# FY.net
KiCad netlist of a schematic drawn in EAGLE
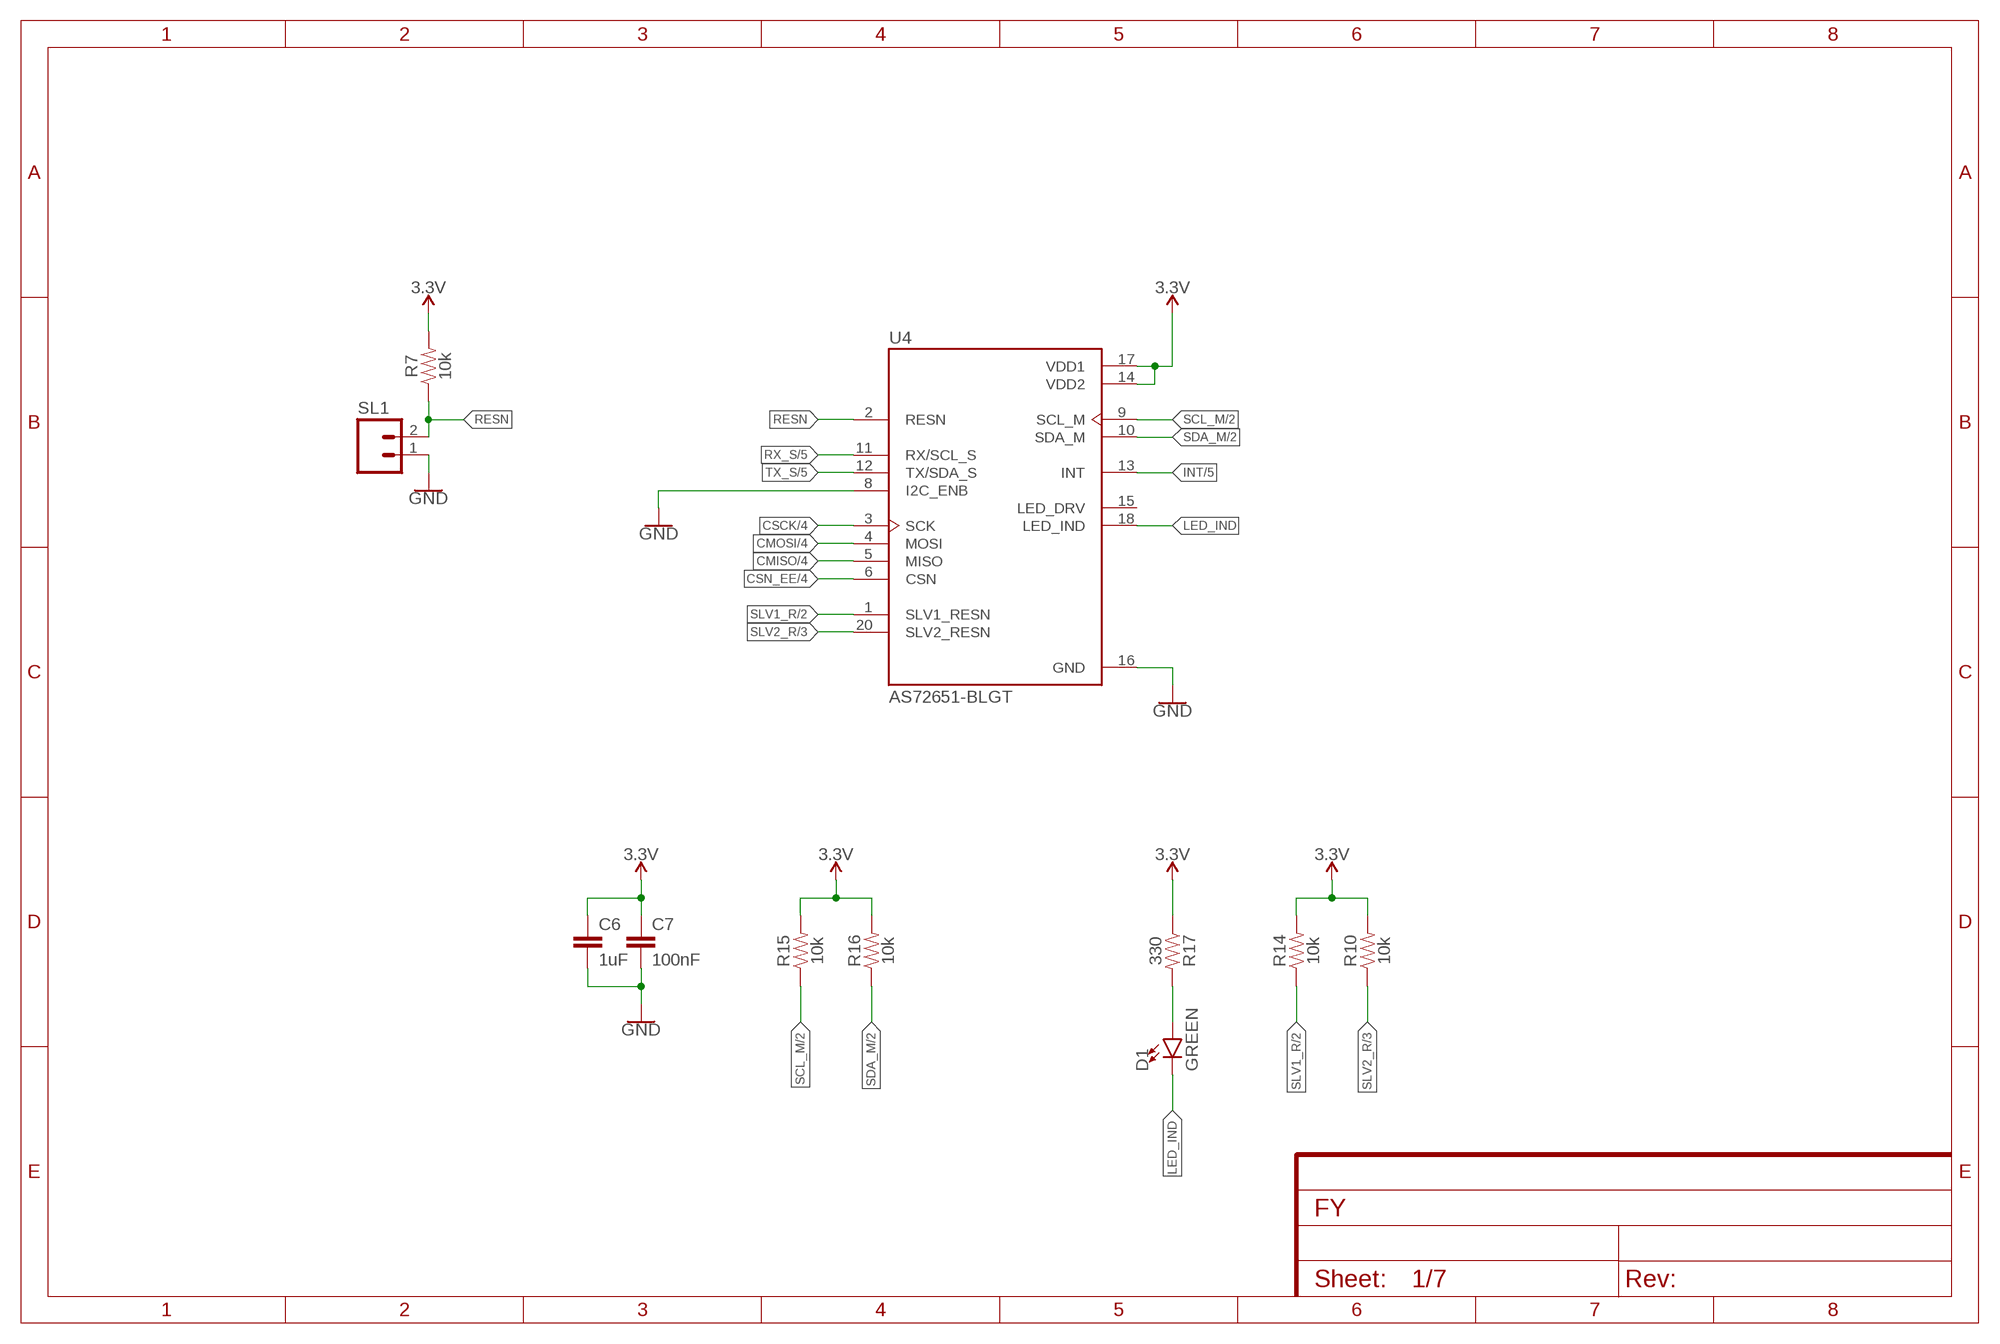
[diagram p0: schematic, sheet 1]
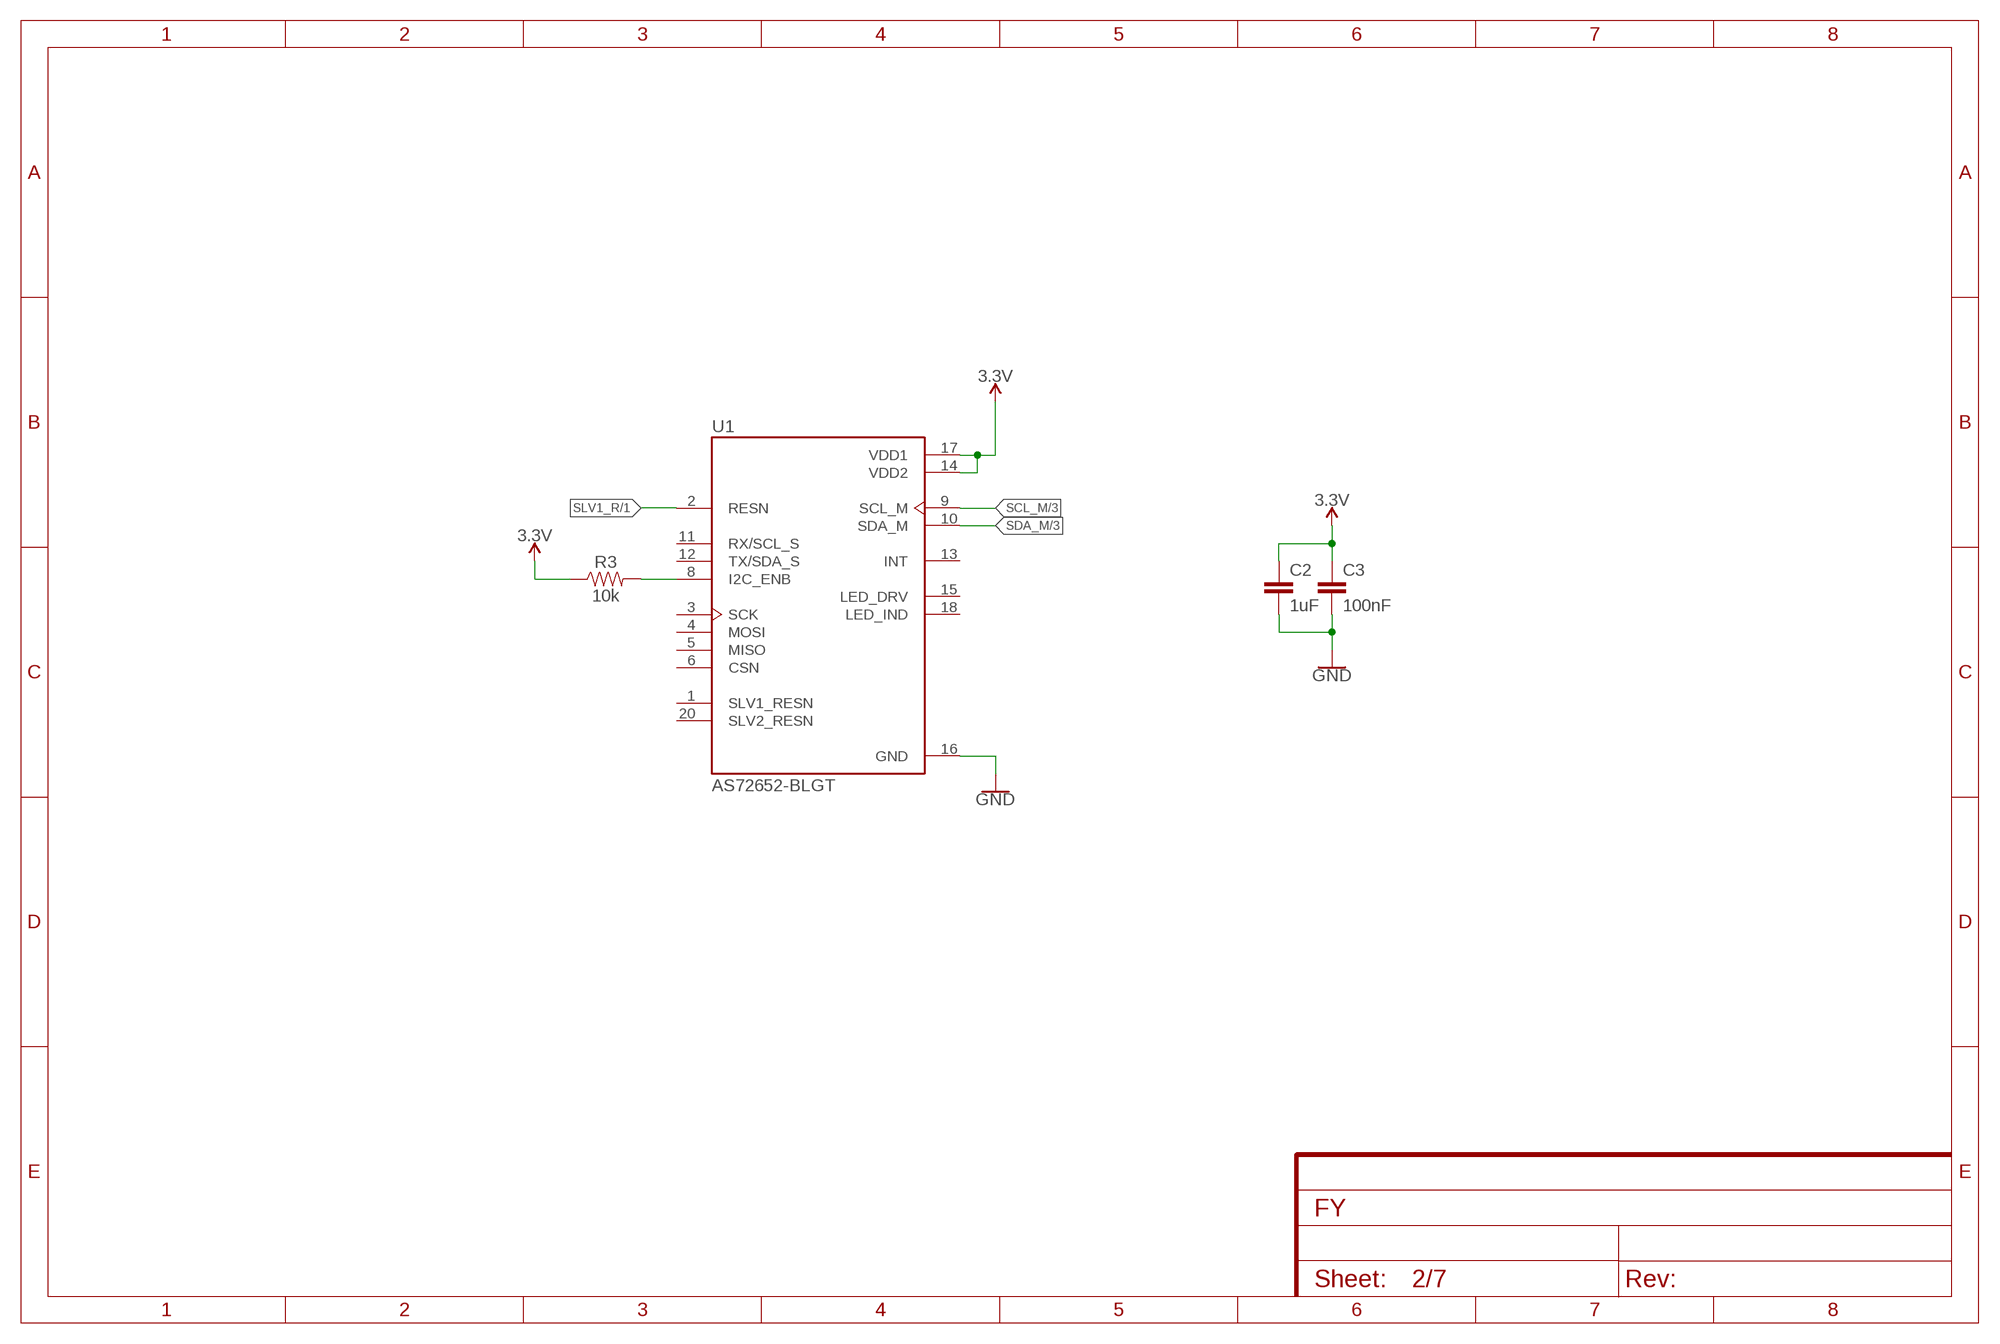
[diagram p1: schematic, sheet 2]
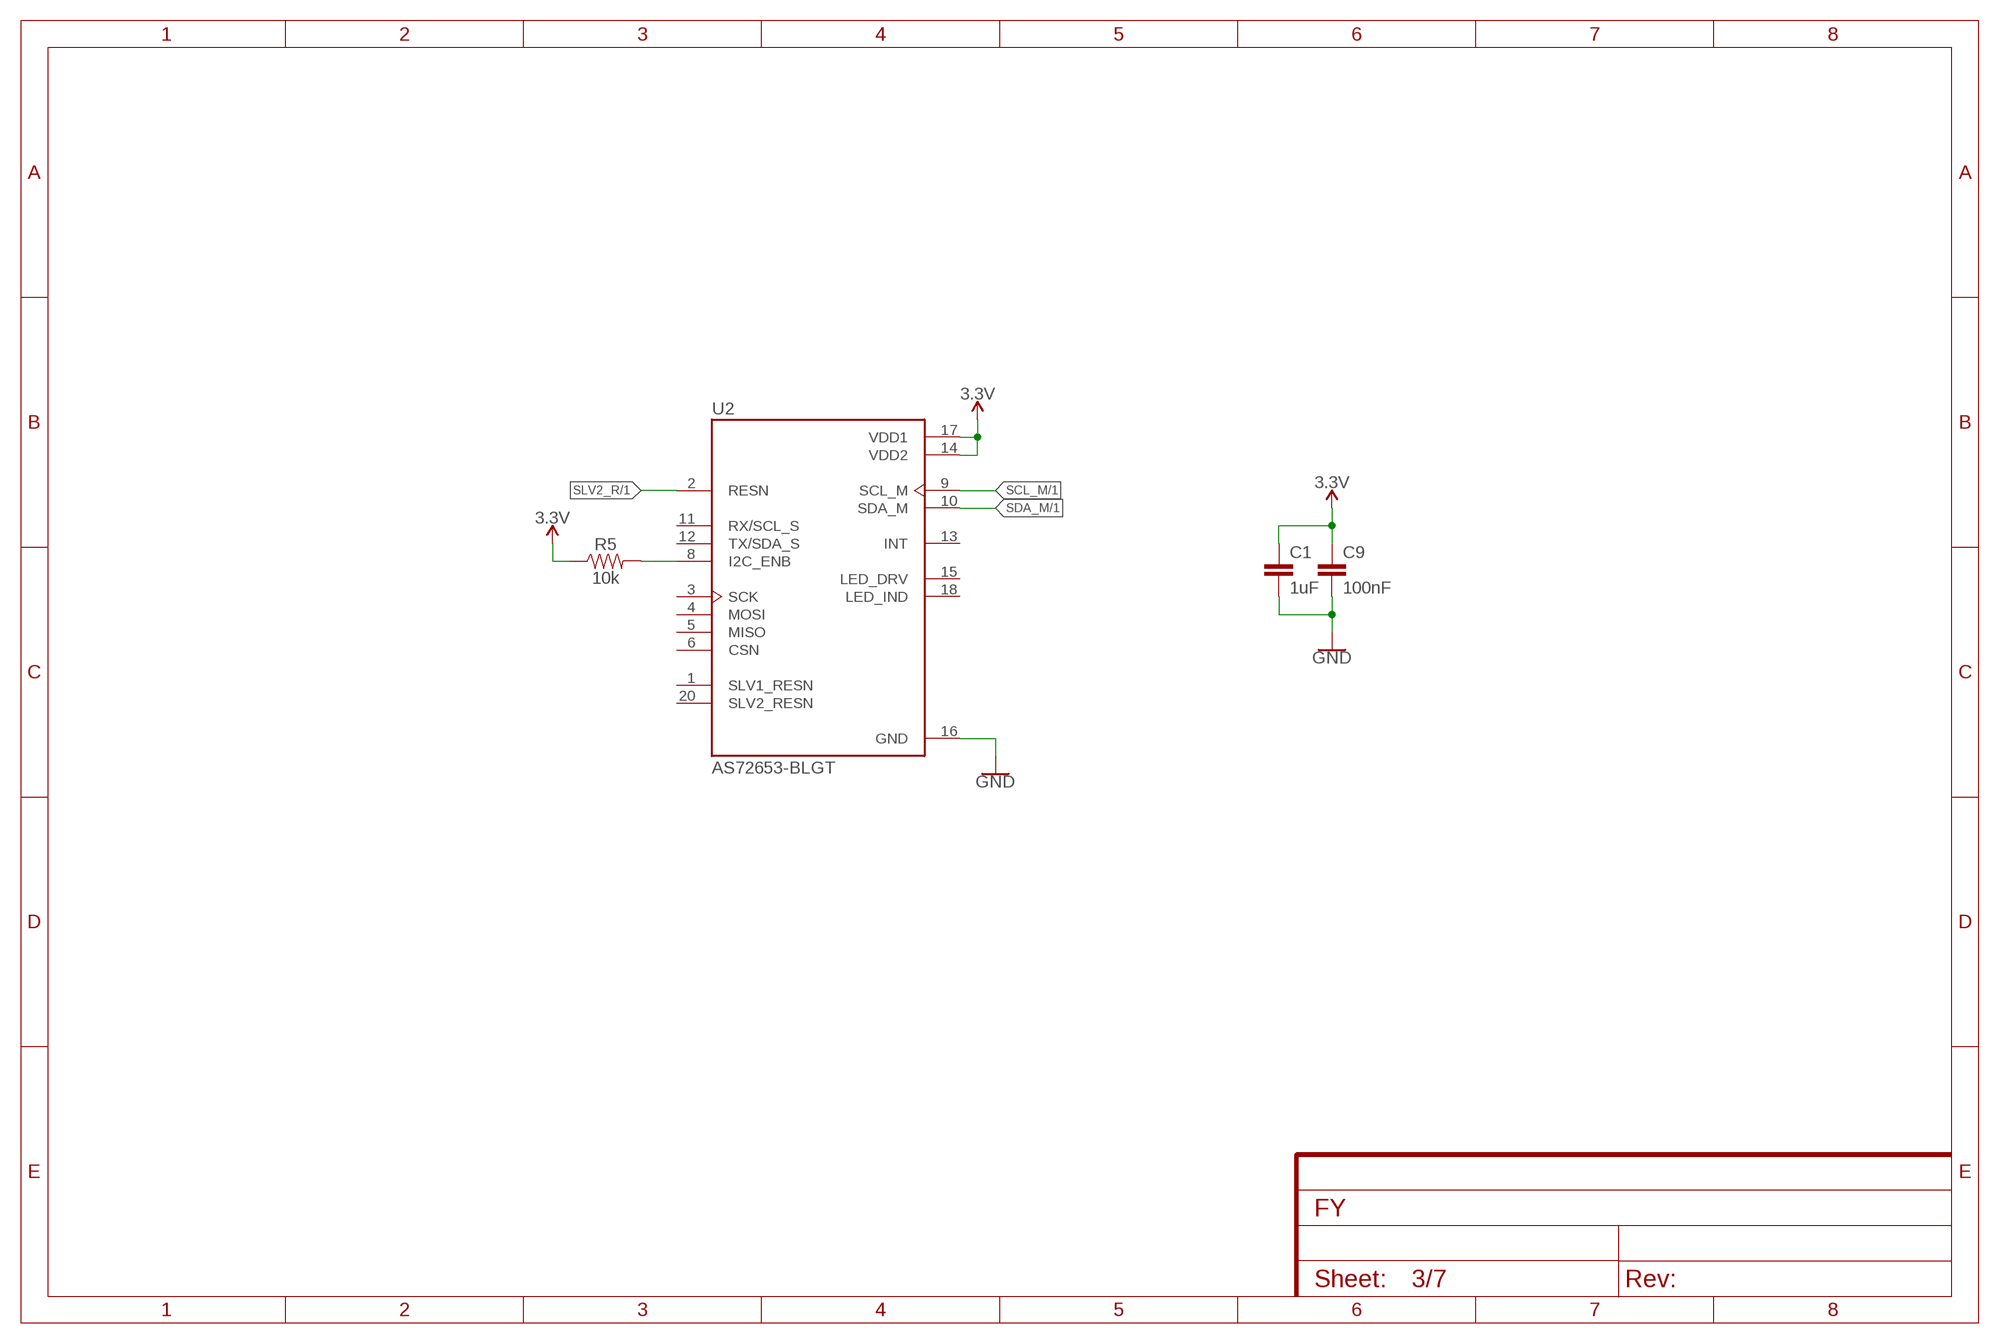
[diagram p2: schematic, sheet 3]
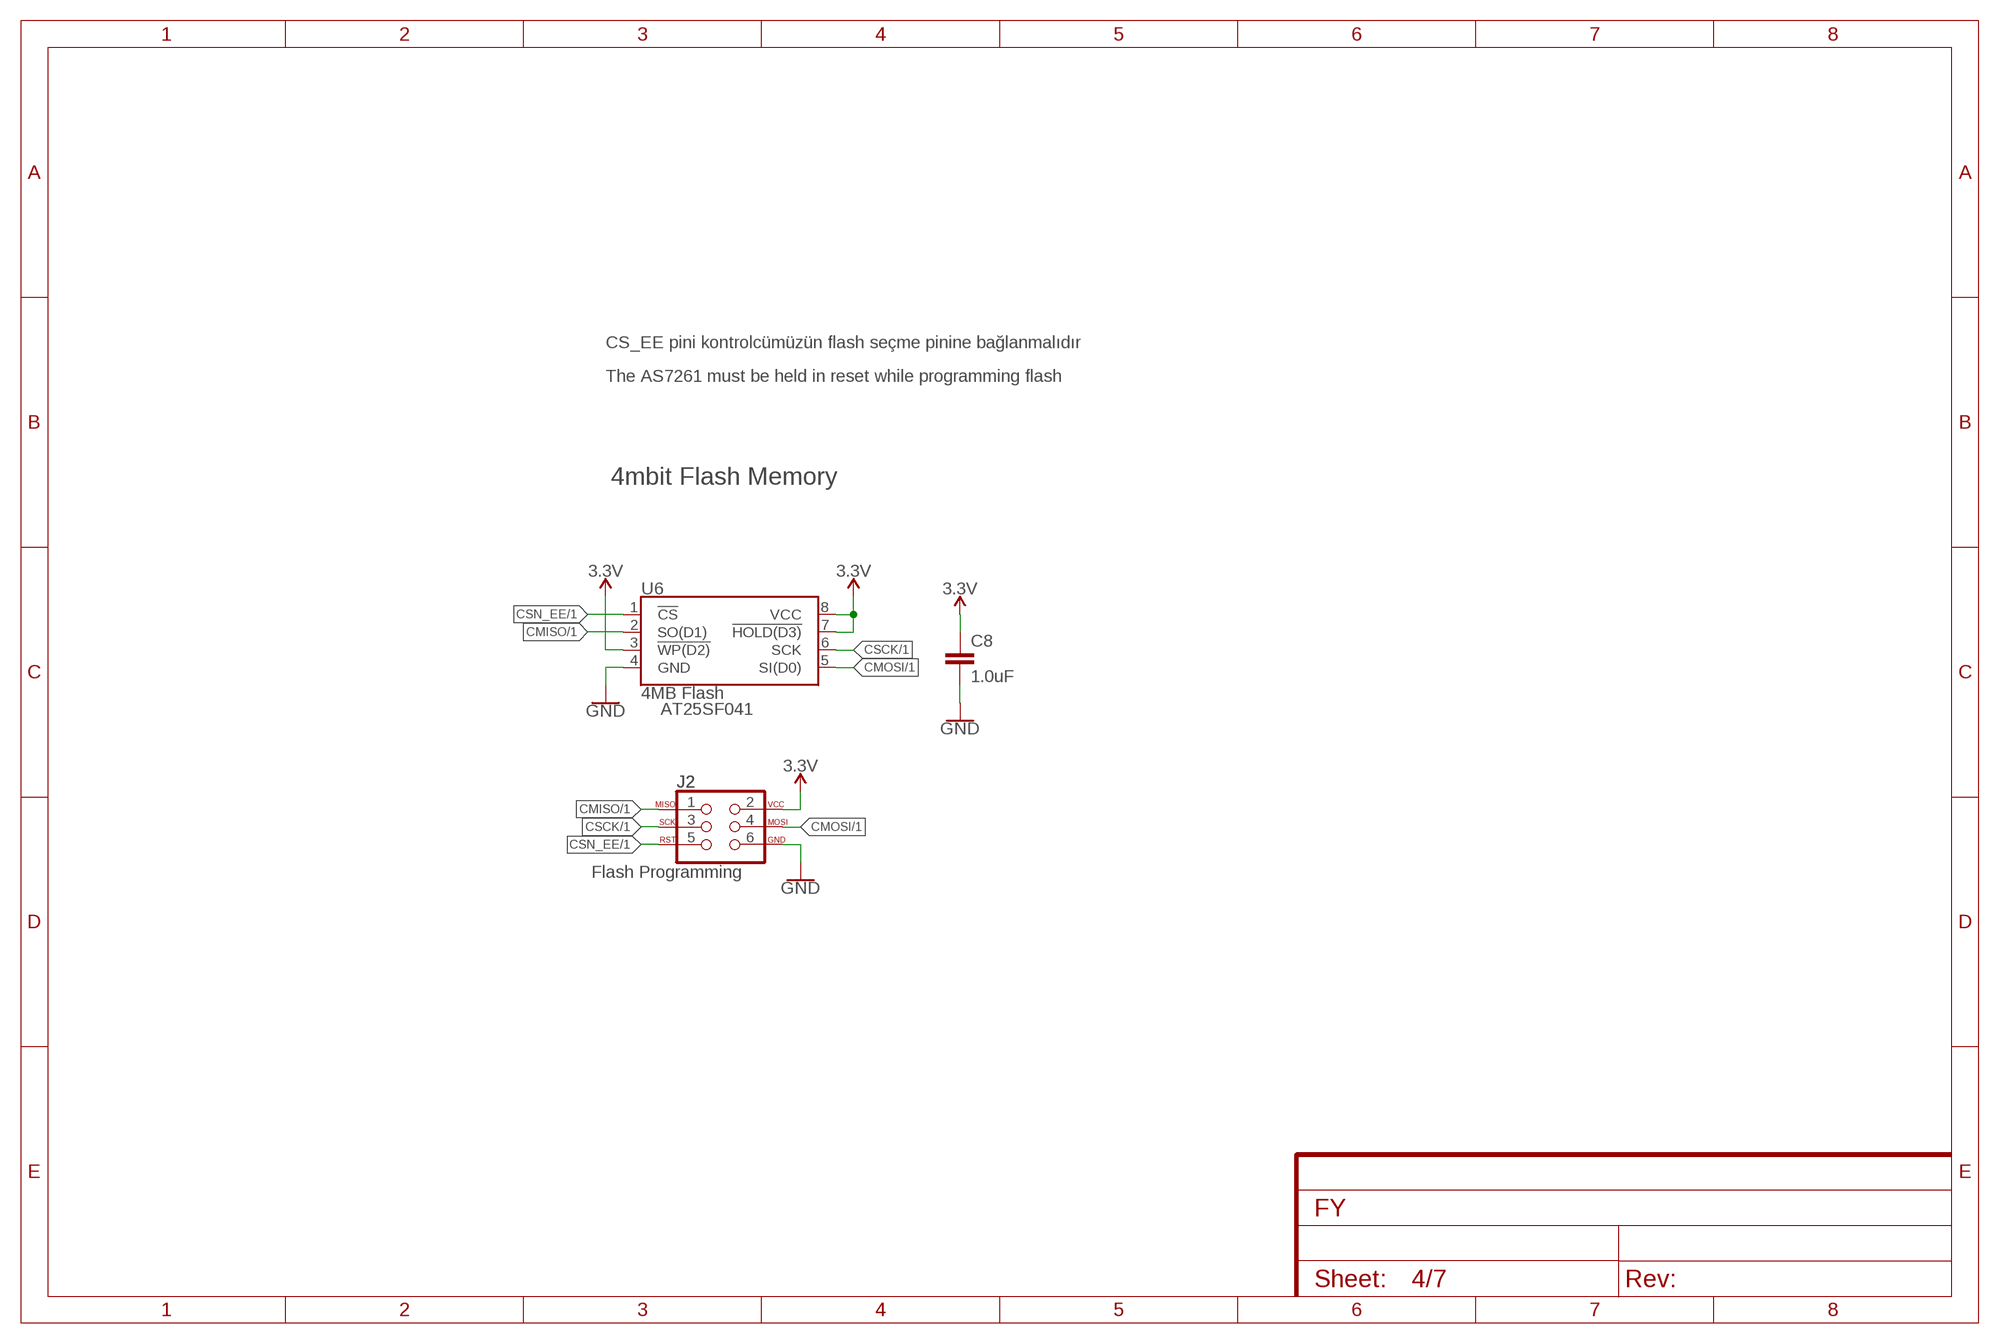
[diagram p3: schematic, sheet 4]
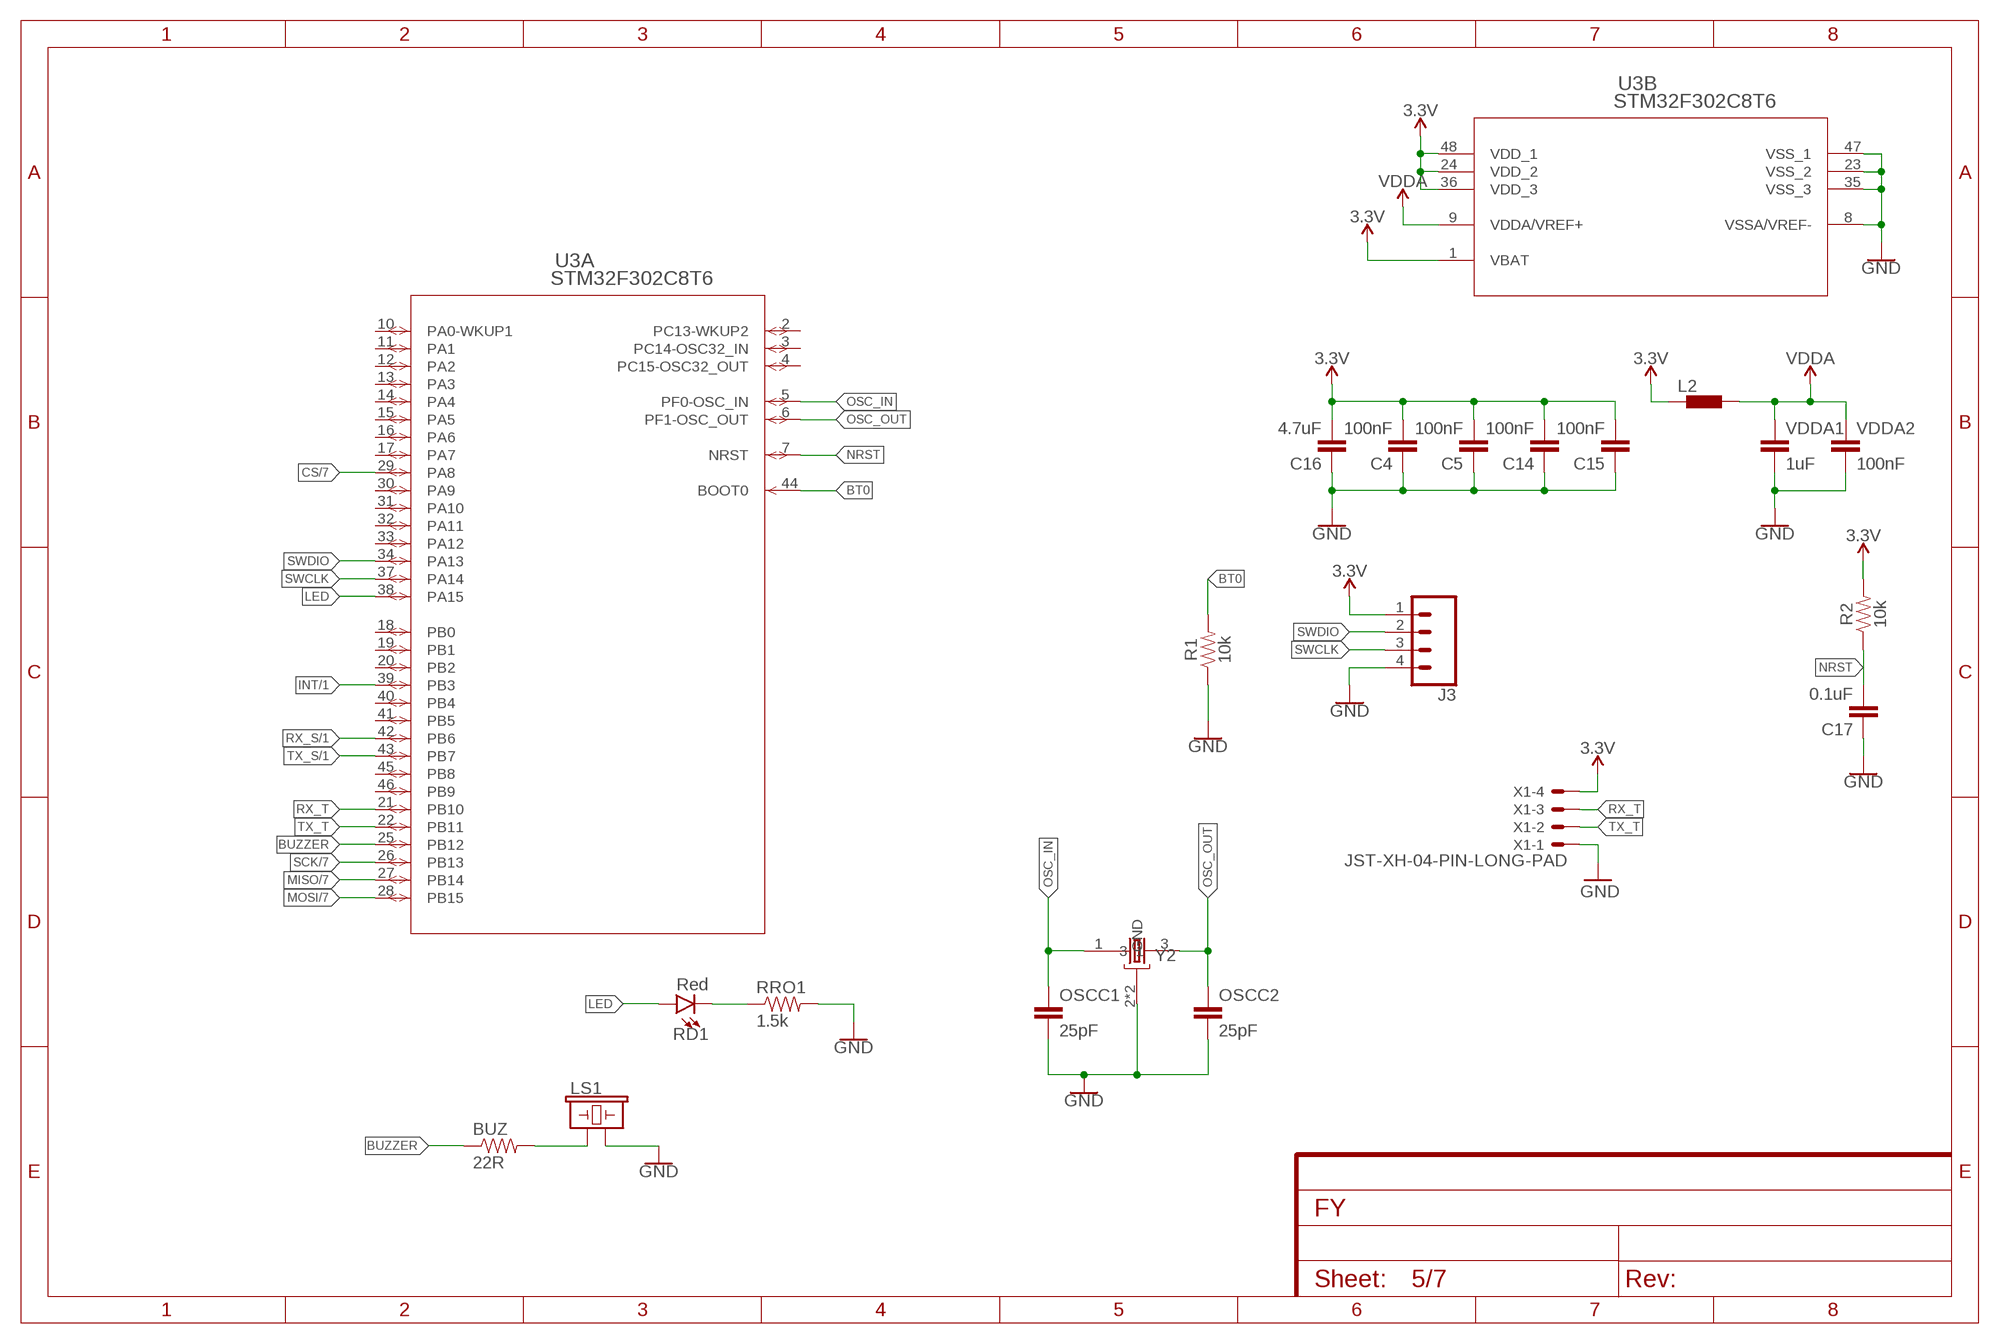
[diagram p4: schematic, sheet 5]
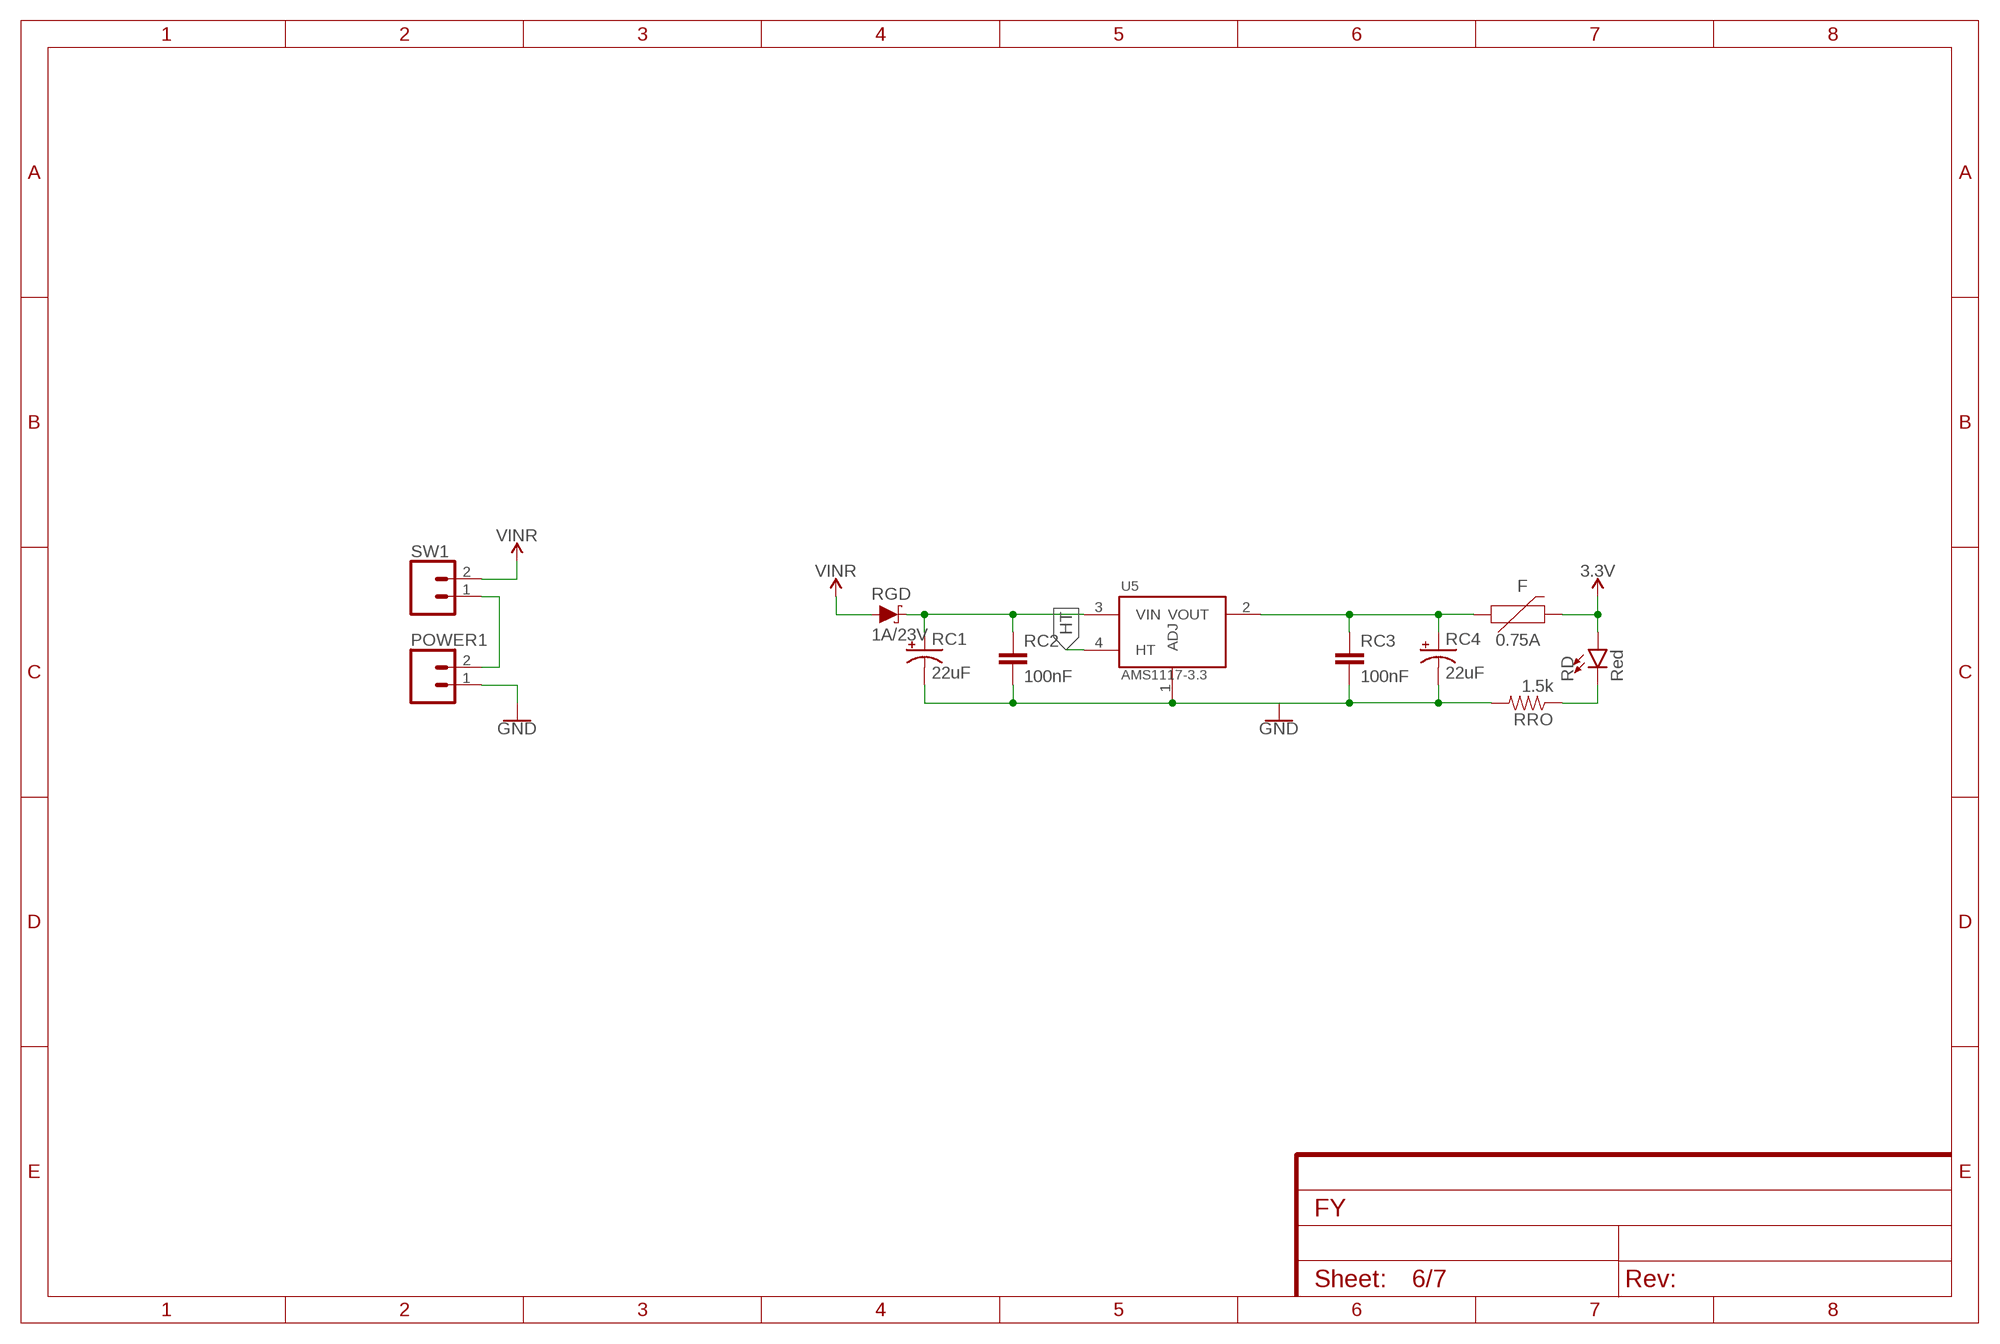
[diagram p5: schematic, sheet 6]
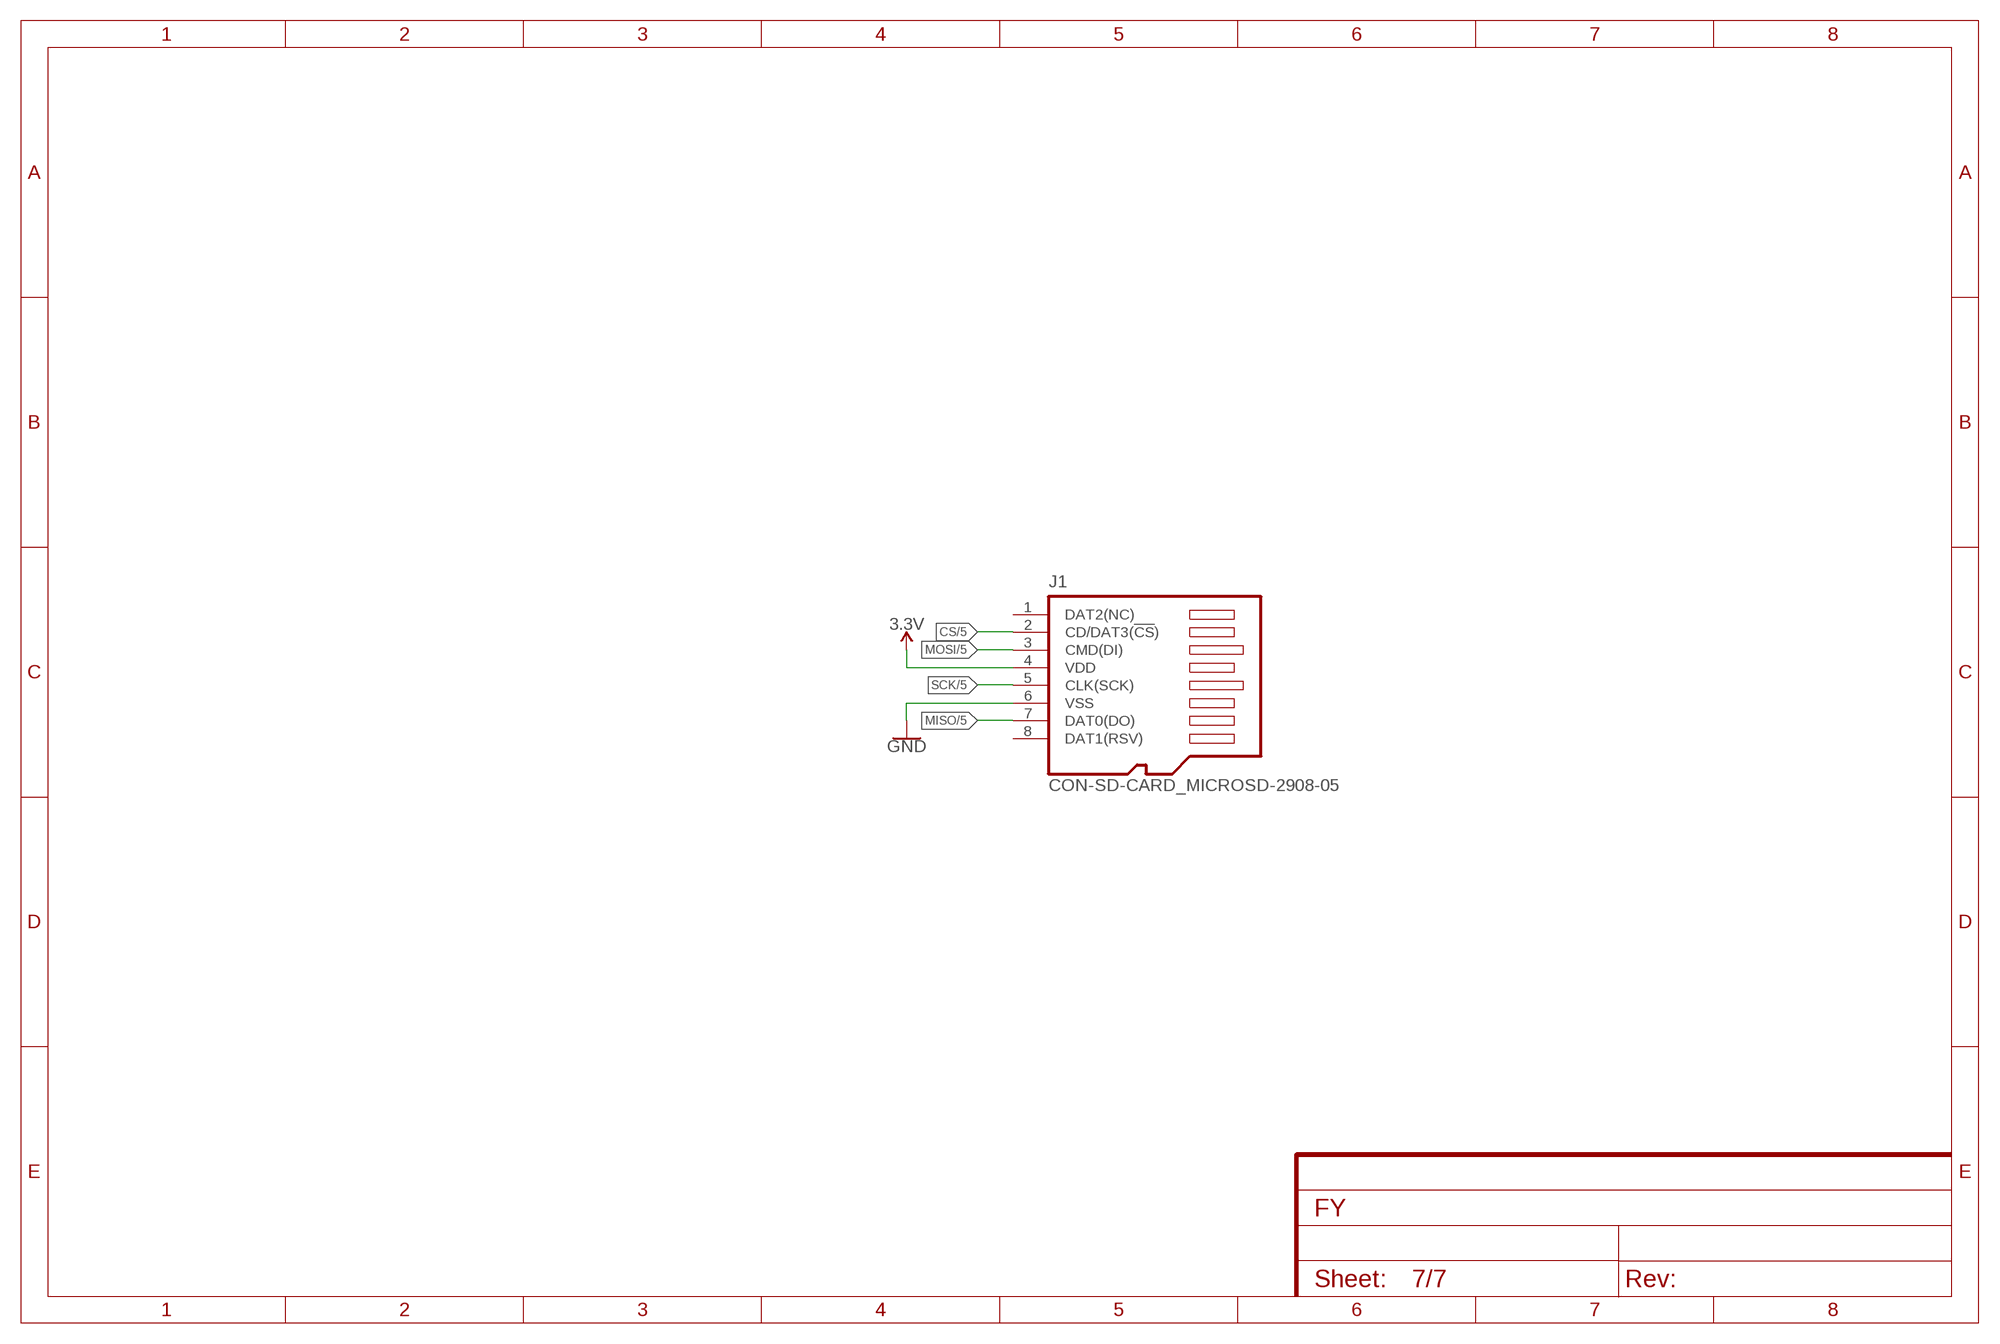
[diagram p6: schematic, sheet 7]

(export (version "E")
  (design (tool "Eeschema 10.0.6"))
  (components
    (comp (ref "C2")
      (value "1uF")
      (footprint "eagle-import:0603")
      (libsource (lib "eagle-import") (part "10UF-0603-6.3V-20%"))
    )
    (comp (ref "C3")
      (value "100nF")
      (footprint "eagle-import:0603")
      (libsource (lib "eagle-import") (part "0.1UF-0603-25V-(+80/-20%)"))
    )
    (comp (ref "R3")
      (value "10k")
      (footprint "eagle-import:0603")
      (libsource (lib "eagle-import") (part "0.05OHM-0603-1/5W-1%"))
    )
    (comp (ref "U1")
      (value "AS72652-BLGT")
      (footprint "eagle-import:PQFN65P470X450X270-20N")
      (fields (field (name "MF") "ams") (field (name "MP") "AS72651-BLGT"))
      (libsource (lib "eagle-import") (part "AS72651-BLGT"))
    )
    (comp (ref "C6")
      (value "1uF")
      (footprint "eagle-import:0603")
      (libsource (lib "eagle-import") (part "10UF-0603-6.3V-20%"))
    )
    (comp (ref "C7")
      (value "100nF")
      (footprint "eagle-import:0603")
      (libsource (lib "eagle-import") (part "0.1UF-0603-25V-(+80/-20%)"))
    )
    (comp (ref "D1")
      (value "GREEN")
      (footprint "eagle-import:LED-0603")
      (libsource (lib "eagle-import") (part "LED-GREEN0603"))
    )
    (comp (ref "R7")
      (value "10k")
      (footprint "eagle-import:0603")
      (libsource (lib "eagle-import") (part "10KOHM-0603-1/10W-1%"))
    )
    (comp (ref "R10")
      (value "10k")
      (footprint "eagle-import:0603")
      (libsource (lib "eagle-import") (part "10KOHM-0603-1/10W-1%"))
    )
    (comp (ref "R14")
      (value "10k")
      (footprint "eagle-import:0603")
      (libsource (lib "eagle-import") (part "10KOHM-0603-1/10W-1%"))
    )
    (comp (ref "R15")
      (value "10k")
      (footprint "eagle-import:0603")
      (libsource (lib "eagle-import") (part "10KOHM-0603-1/10W-1%"))
    )
    (comp (ref "R16")
      (value "10k")
      (footprint "eagle-import:0603")
      (libsource (lib "eagle-import") (part "10KOHM-0603-1/10W-1%"))
    )
    (comp (ref "R17")
      (value "330")
      (footprint "eagle-import:0603")
      (libsource (lib "eagle-import") (part "10KOHM-0603-1/10W-1%"))
    )
    (comp (ref "SL1")
      (value "M02")
      (footprint "eagle-import:02P")
      (libsource (lib "eagle-import") (part "M02"))
    )
    (comp (ref "U4")
      (value "AS72651-BLGT")
      (footprint "eagle-import:PQFN65P470X450X270-20N")
      (fields (field (name "MF") "ams"))
      (libsource (lib "eagle-import") (part "AS72651-BLGT"))
    )
    (comp (ref "J1")
      (value "CON-SD-CARD_MICROSD-2908-05")
      (footprint "eagle-import:CON-SD-CARD_2908-05")
      (libsource (lib "eagle-import") (part "CON-SD-CARD_MICROSD-2908-05"))
    )
    (comp (ref "F")
      (value "0.75A")
      (footprint "eagle-import:1206")
      (libsource (lib "eagle-import") (part "PPTC_THREE-QUARTER-AMP"))
    )
    (comp (ref "POWER1")
      (value "CONN_023.5MM-NO_SILK")
      (footprint "eagle-import:SCREWTERMINAL-3.5MM-2-NS")
      (libsource (lib "eagle-import") (part "CONN_023.5MM-NO_SILK"))
    )
    (comp (ref "RC1")
      (value "22uF")
      (footprint "eagle-import:EIA3528")
      (libsource (lib "eagle-import") (part "10UF-POLAR-EIA3528-20V-10%(TANT)"))
    )
    (comp (ref "RC2")
      (value "100nF")
      (footprint "eagle-import:0603")
      (libsource (lib "eagle-import") (part "SparkFun-Capacitors_510_0.1UF-0603-25V-(+80/-20%)"))
    )
    (comp (ref "RC3")
      (value "100nF")
      (footprint "eagle-import:0603")
      (libsource (lib "eagle-import") (part "SparkFun-Capacitors_510_0.1UF-0603-25V-(+80/-20%)"))
    )
    (comp (ref "RC4")
      (value "22uF")
      (footprint "eagle-import:EIA3528")
      (libsource (lib "eagle-import") (part "10UF-POLAR-EIA3528-20V-10%(TANT)"))
    )
    (comp (ref "RD")
      (value "Red")
      (footprint "eagle-import:LED-0603")
      (libsource (lib "eagle-import") (part "LED-RED0603-SMART"))
    )
    (comp (ref "RGD")
      (value "1A/23V")
      (footprint "eagle-import:SOD-323")
      (libsource (lib "eagle-import") (part "DIODE-SCHOTTKY-BAT20J"))
    )
    (comp (ref "RRO")
      (value "1.5k")
      (footprint "eagle-import:0603-RES")
      (libsource (lib "eagle-import") (part "2.0KOHM1/10W5%(0603)"))
    )
    (comp (ref "SW1")
      (value "CONN_023.5MM-NO_SILK")
      (footprint "eagle-import:SCREWTERMINAL-3.5MM-2-NS")
      (libsource (lib "eagle-import") (part "CONN_023.5MM-NO_SILK"))
    )
    (comp (ref "U5")
      (value "AMS1117-3.3")
      (footprint "eagle-import:SOT229P700X180-4N")
      (fields (field (name "MF") "Advanced Monolithic Systems"))
      (libsource (lib "eagle-import") (part "AMS1117-3.3"))
    )
    (comp (ref "C8")
      (value "1.0uF")
      (footprint "eagle-import:0603")
      (libsource (lib "eagle-import") (part "1.0UF-0603-16V-10%"))
    )
    (comp (ref "J2")
      (value "Flash Programming")
      (footprint "eagle-import:2X3_TEST_POINTS")
      (libsource (lib "eagle-import") (part "AVR_SPI_PROG_3X2TESTPOINTS"))
    )
    (comp (ref "U6")
      (value "4MB Flash")
      (footprint "eagle-import:SO08")
      (libsource (lib "eagle-import") (part "AT25SF041"))
    )
    (comp (ref "C1")
      (value "1uF")
      (footprint "eagle-import:0603")
      (libsource (lib "eagle-import") (part "10UF-0603-6.3V-20%"))
    )
    (comp (ref "C9")
      (value "100nF")
      (footprint "eagle-import:0603")
      (libsource (lib "eagle-import") (part "0.1UF-0603-25V-(+80/-20%)"))
    )
    (comp (ref "R5")
      (value "10k")
      (footprint "eagle-import:0603")
      (libsource (lib "eagle-import") (part "0.05OHM-0603-1/5W-1%"))
    )
    (comp (ref "U2")
      (value "AS72653-BLGT")
      (footprint "eagle-import:PQFN65P470X450X270-20N")
      (fields (field (name "MF") "ams") (field (name "MP") "AS72651-BLGT"))
      (libsource (lib "eagle-import") (part "AS72651-BLGT"))
    )
    (comp (ref "BUZ")
      (value "22R")
      (footprint "eagle-import:0603-RES")
      (libsource (lib "eagle-import") (part "2.0KOHM1/10W5%(0603)"))
    )
    (comp (ref "C4")
      (value "100nF")
      (footprint "eagle-import:0603")
      (libsource (lib "eagle-import") (part "22PF-0603-50V-5%"))
    )
    (comp (ref "C5")
      (value "100nF")
      (footprint "eagle-import:0603")
      (libsource (lib "eagle-import") (part "22PF-0603-50V-5%"))
    )
    (comp (ref "C14")
      (value "100nF")
      (footprint "eagle-import:0603")
      (libsource (lib "eagle-import") (part "22PF-0603-50V-5%"))
    )
    (comp (ref "C15")
      (value "100nF")
      (footprint "eagle-import:0603")
      (libsource (lib "eagle-import") (part "22PF-0603-50V-5%"))
    )
    (comp (ref "C16")
      (value "4.7uF")
      (footprint "eagle-import:0603")
      (libsource (lib "eagle-import") (part "22PF-0603-50V-5%"))
    )
    (comp (ref "C17")
      (value "0.1uF")
      (footprint "eagle-import:0603")
      (libsource (lib "eagle-import") (part "22PF-0603-50V-5%"))
    )
    (comp (ref "J3")
      (value "CONN_04")
      (footprint "eagle-import:1X04")
      (libsource (lib "eagle-import") (part "CONN_04"))
    )
    (comp (ref "L2")
      (value "BLM15HB221SN1")
      (footprint "eagle-import:0402")
      (libsource (lib "eagle-import") (part "BLM15HB221SN1"))
    )
    (comp (ref "LS1")
      (value "BUZZER-PTH")
      (footprint "eagle-import:BUZZER-12MM")
      (libsource (lib "eagle-import") (part "BUZZER-PTH"))
    )
    (comp (ref "OSCC1")
      (value "25pF")
      (footprint "eagle-import:0603")
      (libsource (lib "eagle-import") (part "SparkFun-Capacitors_510_0.1UF-0603-25V-(+80/-20%)"))
    )
    (comp (ref "OSCC2")
      (value "25pF")
      (footprint "eagle-import:0603")
      (libsource (lib "eagle-import") (part "SparkFun-Capacitors_510_0.1UF-0603-25V-(+80/-20%)"))
    )
    (comp (ref "R1")
      (value "10k")
      (footprint "eagle-import:0603")
      (libsource (lib "eagle-import") (part "0.05OHM-0603-1/5W-1%"))
    )
    (comp (ref "R2")
      (value "10k")
      (footprint "eagle-import:0603")
      (libsource (lib "eagle-import") (part "0.05OHM-0603-1/5W-1%"))
    )
    (comp (ref "RD1")
      (value "Red")
      (footprint "eagle-import:LED-0603")
      (libsource (lib "eagle-import") (part "LED-RED0603-SMART"))
    )
    (comp (ref "RRO1")
      (value "1.5k")
      (footprint "eagle-import:0603-RES")
      (libsource (lib "eagle-import") (part "2.0KOHM1/10W5%(0603)"))
    )
    (comp (ref "U3")
      (value "STM32F302C8T6")
      (footprint "eagle-import:LQFP48-7X7MM")
      (fields (field (name "COPYRIGHT") "Copyright (C) 2018 Accelerated Designs. All rights reserved"))
      (libsource (lib "eagle-import") (part "STM32F302C8T6"))
    )
    (comp (ref "VDDA1")
      (value "1uF")
      (footprint "eagle-import:0603")
      (libsource (lib "eagle-import") (part "SparkFun-Capacitors_510_0.1UF-0603-25V-(+80/-20%)"))
    )
    (comp (ref "VDDA2")
      (value "100nF")
      (footprint "eagle-import:0603")
      (libsource (lib "eagle-import") (part "SparkFun-Capacitors_510_0.1UF-0603-25V-(+80/-20%)"))
    )
    (comp (ref "X1")
      (value "JST-XH-04-PIN-LONG-PAD")
      (footprint "eagle-import:JST-XH-04-PACKAGE-LONG-PAD")
      (libsource (lib "eagle-import") (part "JST-XH-04-PIN-LONG-PAD"))
    )
    (comp (ref "Y2")
      (value "ABM2B-8.000MHZ-10-1-U-T")
      (footprint "eagle-import:OSCCC500X320X110-4N")
      (fields (field (name "MF") "Abracon") (field (name "MP") "ABM3B-26.000MHZ-10-1-U-T"))
      (libsource (lib "eagle-import") (part "ABM3B-26.000MHZ-10-1-U-T"))
    )
  )
  (nets
    (net (code "1") (name "3.3V") (class "Default")
      (node (ref "C1") (pin "1") (pinfunction "1_1") (pintype "passive"))
      (node (ref "C14") (pin "2") (pinfunction "2_2") (pintype "passive"))
      (node (ref "C15") (pin "2") (pinfunction "2_2") (pintype "passive"))
      (node (ref "C16") (pin "2") (pinfunction "2_2") (pintype "passive"))
      (node (ref "C2") (pin "1") (pinfunction "1_1") (pintype "passive"))
      (node (ref "C3") (pin "1") (pinfunction "1_1") (pintype "passive"))
      (node (ref "C4") (pin "2") (pinfunction "2_2") (pintype "passive"))
      (node (ref "C5") (pin "2") (pinfunction "2_2") (pintype "passive"))
      (node (ref "C6") (pin "1") (pinfunction "1_1") (pintype "passive"))
      (node (ref "C7") (pin "1") (pinfunction "1_1") (pintype "passive"))
      (node (ref "C8") (pin "1") (pinfunction "1_1") (pintype "passive"))
      (node (ref "C9") (pin "1") (pinfunction "1_1") (pintype "passive"))
      (node (ref "F") (pin "2") (pinfunction "2_2") (pintype "bidirectional"))
      (node (ref "J1") (pin "4") (pinfunction "VDD_4") (pintype "bidirectional"))
      (node (ref "J2") (pin "2") (pinfunction "2_2") (pintype "passive"))
      (node (ref "J3") (pin "1") (pinfunction "1_1") (pintype "passive"))
      (node (ref "L2") (pin "1") (pinfunction "1_1") (pintype "passive"))
      (node (ref "R10") (pin "2") (pinfunction "2_2") (pintype "passive"))
      (node (ref "R14") (pin "2") (pinfunction "2_2") (pintype "passive"))
      (node (ref "R15") (pin "2") (pinfunction "2_2") (pintype "passive"))
      (node (ref "R16") (pin "2") (pinfunction "2_2") (pintype "passive"))
      (node (ref "R17") (pin "1") (pinfunction "1_1") (pintype "passive"))
      (node (ref "R2") (pin "2") (pinfunction "2_2") (pintype "passive"))
      (node (ref "R3") (pin "1") (pinfunction "1_1") (pintype "passive"))
      (node (ref "R5") (pin "1") (pinfunction "1_1") (pintype "passive"))
      (node (ref "R7") (pin "2") (pinfunction "2_2") (pintype "passive"))
      (node (ref "RD") (pin "A") (pinfunction "A_A") (pintype "passive"))
      (node (ref "U1") (pin "14") (pinfunction "VDD2_14") (pintype "power_in"))
      (node (ref "U1") (pin "17") (pinfunction "VDD1_17") (pintype "power_in"))
      (node (ref "U2") (pin "14") (pinfunction "VDD2_14") (pintype "power_in"))
      (node (ref "U2") (pin "17") (pinfunction "VDD1_17") (pintype "power_in"))
      (node (ref "U3") (pin "1") (pinfunction "VBAT_1") (pintype "power_in"))
      (node (ref "U3") (pin "24") (pinfunction "VDD_2_24") (pintype "power_in"))
      (node (ref "U3") (pin "36") (pinfunction "VDD_3_36") (pintype "power_in"))
      (node (ref "U3") (pin "48") (pinfunction "VDD_1_48") (pintype "power_in"))
      (node (ref "U4") (pin "14") (pinfunction "VDD2_14") (pintype "power_in"))
      (node (ref "U4") (pin "17") (pinfunction "VDD1_17") (pintype "power_in"))
      (node (ref "U6") (pin "3") (pinfunction "~{WP(D2})_3") (pintype "bidirectional"))
      (node (ref "U6") (pin "7") (pinfunction "~{HOLD(D3})_7") (pintype "bidirectional"))
      (node (ref "U6") (pin "8") (pinfunction "VCC_8") (pintype "bidirectional"))
      (node (ref "X1") (pin "4") (pinfunction "S_4") (pintype "passive"))
    )
    (net (code "2") (name "BT0") (class "Default")
      (node (ref "R1") (pin "2") (pinfunction "2_2") (pintype "passive"))
      (node (ref "U3") (pin "44") (pinfunction "BOOT0_44") (pintype "input"))
    )
    (net (code "3") (name "BUZZER") (class "Default")
      (node (ref "BUZ") (pin "1") (pinfunction "1_1") (pintype "passive"))
      (node (ref "U3") (pin "25") (pinfunction "PB12_25") (pintype "bidirectional"))
    )
    (net (code "4") (name "CMISO") (class "Default")
      (node (ref "J2") (pin "1") (pinfunction "1_1") (pintype "passive"))
      (node (ref "U4") (pin "5") (pinfunction "MISO_5") (pintype "bidirectional"))
      (node (ref "U6") (pin "2") (pinfunction "SO(D1)_2") (pintype "bidirectional"))
    )
    (net (code "5") (name "CMOSI") (class "Default")
      (node (ref "J2") (pin "4") (pinfunction "4_4") (pintype "passive"))
      (node (ref "U4") (pin "4") (pinfunction "MOSI_4") (pintype "bidirectional"))
      (node (ref "U6") (pin "5") (pinfunction "SI(D0)_5") (pintype "bidirectional"))
    )
    (net (code "6") (name "CS") (class "Default")
      (node (ref "J1") (pin "2") (pinfunction "CD/DAT3(~{CS})_2") (pintype "bidirectional"))
      (node (ref "U3") (pin "29") (pinfunction "PA8_29") (pintype "bidirectional"))
    )
    (net (code "7") (name "CSCK") (class "Default")
      (node (ref "J2") (pin "3") (pinfunction "3_3") (pintype "passive"))
      (node (ref "U4") (pin "3") (pinfunction "SCK_3") (pintype "output"))
      (node (ref "U6") (pin "6") (pinfunction "SCK_6") (pintype "bidirectional"))
    )
    (net (code "8") (name "CSN_EE") (class "Default")
      (node (ref "J2") (pin "5") (pinfunction "5_5") (pintype "passive"))
      (node (ref "U4") (pin "6") (pinfunction "CSN_6") (pintype "output"))
      (node (ref "U6") (pin "1") (pinfunction "~{CS}_1") (pintype "bidirectional"))
    )
    (net (code "9") (name "GND") (class "Default")
      (node (ref "C1") (pin "2") (pinfunction "2_2") (pintype "passive"))
      (node (ref "C14") (pin "1") (pinfunction "1_1") (pintype "passive"))
      (node (ref "C15") (pin "1") (pinfunction "1_1") (pintype "passive"))
      (node (ref "C16") (pin "1") (pinfunction "1_1") (pintype "passive"))
      (node (ref "C17") (pin "1") (pinfunction "1_1") (pintype "passive"))
      (node (ref "C2") (pin "2") (pinfunction "2_2") (pintype "passive"))
      (node (ref "C3") (pin "2") (pinfunction "2_2") (pintype "passive"))
      (node (ref "C4") (pin "1") (pinfunction "1_1") (pintype "passive"))
      (node (ref "C5") (pin "1") (pinfunction "1_1") (pintype "passive"))
      (node (ref "C6") (pin "2") (pinfunction "2_2") (pintype "passive"))
      (node (ref "C7") (pin "2") (pinfunction "2_2") (pintype "passive"))
      (node (ref "C8") (pin "2") (pinfunction "2_2") (pintype "passive"))
      (node (ref "C9") (pin "2") (pinfunction "2_2") (pintype "passive"))
      (node (ref "J1") (pin "6") (pinfunction "VSS_6") (pintype "bidirectional"))
      (node (ref "J2") (pin "6") (pinfunction "6_6") (pintype "passive"))
      (node (ref "J3") (pin "4") (pinfunction "4_4") (pintype "passive"))
      (node (ref "LS1") (pin "-") (pinfunction "2_-") (pintype "passive"))
      (node (ref "OSCC1") (pin "2") (pinfunction "2_2") (pintype "passive"))
      (node (ref "OSCC2") (pin "2") (pinfunction "2_2") (pintype "passive"))
      (node (ref "POWER1") (pin "1") (pinfunction "1_1") (pintype "passive"))
      (node (ref "R1") (pin "1") (pinfunction "1_1") (pintype "passive"))
      (node (ref "RC1") (pin "C") (pinfunction "-_C") (pintype "passive"))
      (node (ref "RC2") (pin "2") (pinfunction "2_2") (pintype "passive"))
      (node (ref "RC3") (pin "2") (pinfunction "2_2") (pintype "passive"))
      (node (ref "RC4") (pin "C") (pinfunction "-_C") (pintype "passive"))
      (node (ref "RRO") (pin "2") (pinfunction "2_2") (pintype "passive"))
      (node (ref "RRO1") (pin "2") (pinfunction "2_2") (pintype "passive"))
      (node (ref "SL1") (pin "1") (pinfunction "1_1") (pintype "passive"))
      (node (ref "U1") (pin "16") (pinfunction "GND_16") (pintype "power_in"))
      (node (ref "U2") (pin "16") (pinfunction "GND_16") (pintype "power_in"))
      (node (ref "U3") (pin "23") (pinfunction "VSS_2_23") (pintype "power_in"))
      (node (ref "U3") (pin "35") (pinfunction "VSS_3_35") (pintype "power_in"))
      (node (ref "U3") (pin "47") (pinfunction "VSS_1_47") (pintype "power_in"))
      (node (ref "U3") (pin "8") (pinfunction "VSSA/VREF-_8") (pintype "power_in"))
      (node (ref "U4") (pin "16") (pinfunction "GND_16") (pintype "power_in"))
      (node (ref "U4") (pin "8") (pinfunction "I2C_ENB_8") (pintype "input"))
      (node (ref "U5") (pin "1") (pinfunction "ADJ_1") (pintype "power_in"))
      (node (ref "U6") (pin "4") (pinfunction "GND_4") (pintype "bidirectional"))
      (node (ref "VDDA1") (pin "2") (pinfunction "2_2") (pintype "passive"))
      (node (ref "VDDA2") (pin "2") (pinfunction "2_2") (pintype "passive"))
      (node (ref "X1") (pin "1") (pinfunction "S_1") (pintype "passive"))
      (node (ref "Y2") (pin "2") (pinfunction "GND_2") (pintype "passive"))
      (node (ref "Y2") (pin "4") (pinfunction "GND_4") (pintype "passive"))
    )
    (net (code "10") (name "HT") (class "Default")
      (node (ref "U5") (pin "4") (pinfunction "HT_4") (pintype "bidirectional"))
    )
    (net (code "11") (name "INT") (class "Default")
      (node (ref "U3") (pin "39") (pinfunction "PB3_39") (pintype "bidirectional"))
      (node (ref "U4") (pin "13") (pinfunction "INT_13") (pintype "output"))
    )
    (net (code "12") (name "LED") (class "Default")
      (node (ref "RD1") (pin "A") (pinfunction "A_A") (pintype "passive"))
      (node (ref "U3") (pin "38") (pinfunction "PA15_38") (pintype "bidirectional"))
    )
    (net (code "13") (name "LED_IND") (class "Default")
      (node (ref "D1") (pin "C") (pinfunction "C_C") (pintype "passive"))
      (node (ref "U4") (pin "18") (pinfunction "LED_IND_18") (pintype "output"))
    )
    (net (code "14") (name "MISO") (class "Default")
      (node (ref "J1") (pin "7") (pinfunction "DAT0(DO)_7") (pintype "bidirectional"))
      (node (ref "U3") (pin "27") (pinfunction "PB14_27") (pintype "bidirectional"))
    )
    (net (code "15") (name "MOSI") (class "Default")
      (node (ref "J1") (pin "3") (pinfunction "CMD(DI)_3") (pintype "bidirectional"))
      (node (ref "U3") (pin "28") (pinfunction "PB15_28") (pintype "bidirectional"))
    )
    (net (code "16") (name "NRST") (class "Default")
      (node (ref "C17") (pin "2") (pinfunction "2_2") (pintype "passive"))
      (node (ref "R2") (pin "1") (pinfunction "1_1") (pintype "passive"))
      (node (ref "U3") (pin "7") (pinfunction "NRST_7") (pintype "bidirectional"))
    )
    (net (code "17") (name "Net-(D1-PadA)") (class "Default")
      (node (ref "D1") (pin "A") (pinfunction "A_A") (pintype "passive"))
      (node (ref "R17") (pin "2") (pinfunction "2_2") (pintype "passive"))
    )
    (net (code "18") (name "Net-(LS1-1)") (class "Default")
      (node (ref "BUZ") (pin "2") (pinfunction "2_2") (pintype "passive"))
      (node (ref "LS1") (pin "+") (pinfunction "1_+") (pintype "passive"))
    )
    (net (code "19") (name "Net-(POWER1-Pad2)") (class "Default")
      (node (ref "POWER1") (pin "2") (pinfunction "2_2") (pintype "passive"))
      (node (ref "SW1") (pin "1") (pinfunction "1_1") (pintype "passive"))
    )
    (net (code "20") (name "Net-(RC1-+)") (class "Default")
      (node (ref "RC1") (pin "A") (pinfunction "+_A") (pintype "passive"))
      (node (ref "RC2") (pin "1") (pinfunction "1_1") (pintype "passive"))
      (node (ref "RGD") (pin "C") (pinfunction "C_C") (pintype "passive"))
      (node (ref "U5") (pin "3") (pinfunction "VIN_3") (pintype "input"))
    )
    (net (code "21") (name "Net-(RC4-+)") (class "Default")
      (node (ref "F") (pin "1") (pinfunction "1_1") (pintype "bidirectional"))
      (node (ref "RC3") (pin "1") (pinfunction "1_1") (pintype "passive"))
      (node (ref "RC4") (pin "A") (pinfunction "+_A") (pintype "passive"))
      (node (ref "U5") (pin "2") (pinfunction "VOUT_2") (pintype "output"))
    )
    (net (code "22") (name "Net-(RD-PadC)") (class "Default")
      (node (ref "RD") (pin "C") (pinfunction "C_C") (pintype "passive"))
      (node (ref "RRO") (pin "1") (pinfunction "1_1") (pintype "passive"))
    )
    (net (code "23") (name "Net-(RD1-PadC)") (class "Default")
      (node (ref "RD1") (pin "C") (pinfunction "C_C") (pintype "passive"))
      (node (ref "RRO1") (pin "1") (pinfunction "1_1") (pintype "passive"))
    )
    (net (code "24") (name "Net-(U1-I2C_ENB)") (class "Default")
      (node (ref "R3") (pin "2") (pinfunction "2_2") (pintype "passive"))
      (node (ref "U1") (pin "8") (pinfunction "I2C_ENB_8") (pintype "input"))
    )
    (net (code "25") (name "Net-(U2-I2C_ENB)") (class "Default")
      (node (ref "R5") (pin "2") (pinfunction "2_2") (pintype "passive"))
      (node (ref "U2") (pin "8") (pinfunction "I2C_ENB_8") (pintype "input"))
    )
    (net (code "26") (name "OSC_IN") (class "Default")
      (node (ref "OSCC1") (pin "1") (pinfunction "1_1") (pintype "passive"))
      (node (ref "U3") (pin "5") (pinfunction "PF0-OSC_IN_5") (pintype "bidirectional"))
      (node (ref "Y2") (pin "1") (pinfunction "1_1") (pintype "passive"))
    )
    (net (code "27") (name "OSC_OUT") (class "Default")
      (node (ref "OSCC2") (pin "1") (pinfunction "1_1") (pintype "passive"))
      (node (ref "U3") (pin "6") (pinfunction "PF1-OSC_OUT_6") (pintype "bidirectional"))
      (node (ref "Y2") (pin "3") (pinfunction "3_3") (pintype "passive"))
    )
    (net (code "28") (name "RESN") (class "Default")
      (node (ref "R7") (pin "1") (pinfunction "1_1") (pintype "passive"))
      (node (ref "SL1") (pin "2") (pinfunction "2_2") (pintype "passive"))
      (node (ref "U4") (pin "2") (pinfunction "RESN_2") (pintype "input"))
    )
    (net (code "29") (name "RX_S") (class "Default")
      (node (ref "U3") (pin "42") (pinfunction "PB6_42") (pintype "bidirectional"))
      (node (ref "U4") (pin "11") (pinfunction "RX/SCL_S_11") (pintype "bidirectional"))
    )
    (net (code "30") (name "RX_T") (class "Default")
      (node (ref "U3") (pin "21") (pinfunction "PB10_21") (pintype "bidirectional"))
      (node (ref "X1") (pin "3") (pinfunction "S_3") (pintype "passive"))
    )
    (net (code "31") (name "SCK") (class "Default")
      (node (ref "J1") (pin "5") (pinfunction "CLK(SCK)_5") (pintype "bidirectional"))
      (node (ref "U3") (pin "26") (pinfunction "PB13_26") (pintype "bidirectional"))
    )
    (net (code "32") (name "SCL_M") (class "Default")
      (node (ref "R15") (pin "1") (pinfunction "1_1") (pintype "passive"))
      (node (ref "U1") (pin "9") (pinfunction "SCL_M_9") (pintype "output"))
      (node (ref "U2") (pin "9") (pinfunction "SCL_M_9") (pintype "output"))
      (node (ref "U4") (pin "9") (pinfunction "SCL_M_9") (pintype "output"))
    )
    (net (code "33") (name "SDA_M") (class "Default")
      (node (ref "R16") (pin "1") (pinfunction "1_1") (pintype "passive"))
      (node (ref "U1") (pin "10") (pinfunction "SDA_M_10") (pintype "bidirectional"))
      (node (ref "U2") (pin "10") (pinfunction "SDA_M_10") (pintype "bidirectional"))
      (node (ref "U4") (pin "10") (pinfunction "SDA_M_10") (pintype "bidirectional"))
    )
    (net (code "34") (name "SLV1_R") (class "Default")
      (node (ref "R14") (pin "1") (pinfunction "1_1") (pintype "passive"))
      (node (ref "U1") (pin "2") (pinfunction "RESN_2") (pintype "input"))
      (node (ref "U4") (pin "1") (pinfunction "SLV1_RESN_1") (pintype "bidirectional"))
    )
    (net (code "35") (name "SLV2_R") (class "Default")
      (node (ref "R10") (pin "1") (pinfunction "1_1") (pintype "passive"))
      (node (ref "U2") (pin "2") (pinfunction "RESN_2") (pintype "input"))
      (node (ref "U4") (pin "20") (pinfunction "SLV2_RESN_20") (pintype "output"))
    )
    (net (code "36") (name "SWCLK") (class "Default")
      (node (ref "J3") (pin "3") (pinfunction "3_3") (pintype "passive"))
      (node (ref "U3") (pin "37") (pinfunction "PA14_37") (pintype "bidirectional"))
    )
    (net (code "37") (name "SWDIO") (class "Default")
      (node (ref "J3") (pin "2") (pinfunction "2_2") (pintype "passive"))
      (node (ref "U3") (pin "34") (pinfunction "PA13_34") (pintype "bidirectional"))
    )
    (net (code "38") (name "TX_S") (class "Default")
      (node (ref "U3") (pin "43") (pinfunction "PB7_43") (pintype "bidirectional"))
      (node (ref "U4") (pin "12") (pinfunction "TX/SDA_S_12") (pintype "bidirectional"))
    )
    (net (code "39") (name "TX_T") (class "Default")
      (node (ref "U3") (pin "22") (pinfunction "PB11_22") (pintype "bidirectional"))
      (node (ref "X1") (pin "2") (pinfunction "S_2") (pintype "passive"))
    )
    (net (code "40") (name "VDDA") (class "Default")
      (node (ref "L2") (pin "2") (pinfunction "2_2") (pintype "passive"))
      (node (ref "U3") (pin "9") (pinfunction "VDDA/VREF+_9") (pintype "power_in"))
      (node (ref "VDDA1") (pin "1") (pinfunction "1_1") (pintype "passive"))
      (node (ref "VDDA2") (pin "1") (pinfunction "1_1") (pintype "passive"))
    )
    (net (code "41") (name "VIN") (class "Default")
      (node (ref "RGD") (pin "A") (pinfunction "A_A") (pintype "passive"))
      (node (ref "SW1") (pin "2") (pinfunction "2_2") (pintype "passive"))
    )
    (net (code "42") (name "unconnected-(J1B-DAT1(RSV)-Pad8)") (class "Default")
      (node (ref "J1") (pin "8") (pinfunction "DAT1(RSV)_8") (pintype "bidirectional"))
    )
    (net (code "43") (name "unconnected-(J1B-DAT2(NC)-Pad1)") (class "Default")
      (node (ref "J1") (pin "1") (pinfunction "DAT2(NC)_1") (pintype "bidirectional"))
    )
    (net (code "44") (name "unconnected-(U1-CSN-Pad6)") (class "Default")
      (node (ref "U1") (pin "6") (pinfunction "CSN_6") (pintype "output"))
    )
    (net (code "45") (name "unconnected-(U1-INT-Pad13)") (class "Default")
      (node (ref "U1") (pin "13") (pinfunction "INT_13") (pintype "output"))
    )
    (net (code "46") (name "unconnected-(U1-LED_DRV-Pad15)") (class "Default")
      (node (ref "U1") (pin "15") (pinfunction "LED_DRV_15") (pintype "output"))
    )
    (net (code "47") (name "unconnected-(U1-LED_IND-Pad18)") (class "Default")
      (node (ref "U1") (pin "18") (pinfunction "LED_IND_18") (pintype "output"))
    )
    (net (code "48") (name "unconnected-(U1-MISO-Pad5)") (class "Default")
      (node (ref "U1") (pin "5") (pinfunction "MISO_5") (pintype "bidirectional"))
    )
    (net (code "49") (name "unconnected-(U1-MOSI-Pad4)") (class "Default")
      (node (ref "U1") (pin "4") (pinfunction "MOSI_4") (pintype "bidirectional"))
    )
    (net (code "50") (name "unconnected-(U1-RX{slash}SCL_S-Pad11)") (class "Default")
      (node (ref "U1") (pin "11") (pinfunction "RX/SCL_S_11") (pintype "bidirectional"))
    )
    (net (code "51") (name "unconnected-(U1-SCK-Pad3)") (class "Default")
      (node (ref "U1") (pin "3") (pinfunction "SCK_3") (pintype "output"))
    )
    (net (code "52") (name "unconnected-(U1-SLV1_RESN-Pad1)") (class "Default")
      (node (ref "U1") (pin "1") (pinfunction "SLV1_RESN_1") (pintype "bidirectional"))
    )
    (net (code "53") (name "unconnected-(U1-SLV2_RESN-Pad20)") (class "Default")
      (node (ref "U1") (pin "20") (pinfunction "SLV2_RESN_20") (pintype "output"))
    )
    (net (code "54") (name "unconnected-(U1-TX{slash}SDA_S-Pad12)") (class "Default")
      (node (ref "U1") (pin "12") (pinfunction "TX/SDA_S_12") (pintype "bidirectional"))
    )
    (net (code "55") (name "unconnected-(U2-CSN-Pad6)") (class "Default")
      (node (ref "U2") (pin "6") (pinfunction "CSN_6") (pintype "output"))
    )
    (net (code "56") (name "unconnected-(U2-INT-Pad13)") (class "Default")
      (node (ref "U2") (pin "13") (pinfunction "INT_13") (pintype "output"))
    )
    (net (code "57") (name "unconnected-(U2-LED_DRV-Pad15)") (class "Default")
      (node (ref "U2") (pin "15") (pinfunction "LED_DRV_15") (pintype "output"))
    )
    (net (code "58") (name "unconnected-(U2-LED_IND-Pad18)") (class "Default")
      (node (ref "U2") (pin "18") (pinfunction "LED_IND_18") (pintype "output"))
    )
    (net (code "59") (name "unconnected-(U2-MISO-Pad5)") (class "Default")
      (node (ref "U2") (pin "5") (pinfunction "MISO_5") (pintype "bidirectional"))
    )
    (net (code "60") (name "unconnected-(U2-MOSI-Pad4)") (class "Default")
      (node (ref "U2") (pin "4") (pinfunction "MOSI_4") (pintype "bidirectional"))
    )
    (net (code "61") (name "unconnected-(U2-RX{slash}SCL_S-Pad11)") (class "Default")
      (node (ref "U2") (pin "11") (pinfunction "RX/SCL_S_11") (pintype "bidirectional"))
    )
    (net (code "62") (name "unconnected-(U2-SCK-Pad3)") (class "Default")
      (node (ref "U2") (pin "3") (pinfunction "SCK_3") (pintype "output"))
    )
    (net (code "63") (name "unconnected-(U2-SLV1_RESN-Pad1)") (class "Default")
      (node (ref "U2") (pin "1") (pinfunction "SLV1_RESN_1") (pintype "bidirectional"))
    )
    (net (code "64") (name "unconnected-(U2-SLV2_RESN-Pad20)") (class "Default")
      (node (ref "U2") (pin "20") (pinfunction "SLV2_RESN_20") (pintype "output"))
    )
    (net (code "65") (name "unconnected-(U2-TX{slash}SDA_S-Pad12)") (class "Default")
      (node (ref "U2") (pin "12") (pinfunction "TX/SDA_S_12") (pintype "bidirectional"))
    )
    (net (code "66") (name "unconnected-(U3A-PA0-WKUP1-Pad10)") (class "Default")
      (node (ref "U3") (pin "10") (pinfunction "PA0-WKUP1_10") (pintype "bidirectional"))
    )
    (net (code "67") (name "unconnected-(U3A-PA1-Pad11)") (class "Default")
      (node (ref "U3") (pin "11") (pinfunction "PA1_11") (pintype "bidirectional"))
    )
    (net (code "68") (name "unconnected-(U3A-PA2-Pad12)") (class "Default")
      (node (ref "U3") (pin "12") (pinfunction "PA2_12") (pintype "bidirectional"))
    )
    (net (code "69") (name "unconnected-(U3A-PA3-Pad13)") (class "Default")
      (node (ref "U3") (pin "13") (pinfunction "PA3_13") (pintype "bidirectional"))
    )
    (net (code "70") (name "unconnected-(U3A-PA4-Pad14)") (class "Default")
      (node (ref "U3") (pin "14") (pinfunction "PA4_14") (pintype "bidirectional"))
    )
    (net (code "71") (name "unconnected-(U3A-PA5-Pad15)") (class "Default")
      (node (ref "U3") (pin "15") (pinfunction "PA5_15") (pintype "bidirectional"))
    )
    (net (code "72") (name "unconnected-(U3A-PA6-Pad16)") (class "Default")
      (node (ref "U3") (pin "16") (pinfunction "PA6_16") (pintype "bidirectional"))
    )
    (net (code "73") (name "unconnected-(U3A-PA7-Pad17)") (class "Default")
      (node (ref "U3") (pin "17") (pinfunction "PA7_17") (pintype "bidirectional"))
    )
    (net (code "74") (name "unconnected-(U3A-PA9-Pad30)") (class "Default")
      (node (ref "U3") (pin "30") (pinfunction "PA9_30") (pintype "bidirectional"))
    )
    (net (code "75") (name "unconnected-(U3A-PA10-Pad31)") (class "Default")
      (node (ref "U3") (pin "31") (pinfunction "PA10_31") (pintype "bidirectional"))
    )
    (net (code "76") (name "unconnected-(U3A-PA11-Pad32)") (class "Default")
      (node (ref "U3") (pin "32") (pinfunction "PA11_32") (pintype "bidirectional"))
    )
    (net (code "77") (name "unconnected-(U3A-PA12-Pad33)") (class "Default")
      (node (ref "U3") (pin "33") (pinfunction "PA12_33") (pintype "bidirectional"))
    )
    (net (code "78") (name "unconnected-(U3A-PB0-Pad18)") (class "Default")
      (node (ref "U3") (pin "18") (pinfunction "PB0_18") (pintype "bidirectional"))
    )
    (net (code "79") (name "unconnected-(U3A-PB1-Pad19)") (class "Default")
      (node (ref "U3") (pin "19") (pinfunction "PB1_19") (pintype "bidirectional"))
    )
    (net (code "80") (name "unconnected-(U3A-PB2-Pad20)") (class "Default")
      (node (ref "U3") (pin "20") (pinfunction "PB2_20") (pintype "bidirectional"))
    )
    (net (code "81") (name "unconnected-(U3A-PB4-Pad40)") (class "Default")
      (node (ref "U3") (pin "40") (pinfunction "PB4_40") (pintype "bidirectional"))
    )
    (net (code "82") (name "unconnected-(U3A-PB5-Pad41)") (class "Default")
      (node (ref "U3") (pin "41") (pinfunction "PB5_41") (pintype "bidirectional"))
    )
    (net (code "83") (name "unconnected-(U3A-PB8-Pad45)") (class "Default")
      (node (ref "U3") (pin "45") (pinfunction "PB8_45") (pintype "bidirectional"))
    )
    (net (code "84") (name "unconnected-(U3A-PB9-Pad46)") (class "Default")
      (node (ref "U3") (pin "46") (pinfunction "PB9_46") (pintype "bidirectional"))
    )
    (net (code "85") (name "unconnected-(U3A-PC13-WKUP2-Pad2)") (class "Default")
      (node (ref "U3") (pin "2") (pinfunction "PC13-WKUP2_2") (pintype "bidirectional"))
    )
    (net (code "86") (name "unconnected-(U3A-PC14-OSC32_IN-Pad3)") (class "Default")
      (node (ref "U3") (pin "3") (pinfunction "PC14-OSC32_IN_3") (pintype "bidirectional"))
    )
    (net (code "87") (name "unconnected-(U3A-PC15-OSC32_OUT-Pad4)") (class "Default")
      (node (ref "U3") (pin "4") (pinfunction "PC15-OSC32_OUT_4") (pintype "bidirectional"))
    )
    (net (code "88") (name "unconnected-(U4-LED_DRV-Pad15)") (class "Default")
      (node (ref "U4") (pin "15") (pinfunction "LED_DRV_15") (pintype "output"))
    )
  )
)
